# EasyGate1541_DIP-40.net
KiCad netlist of a schematic drawn in Altium Designer
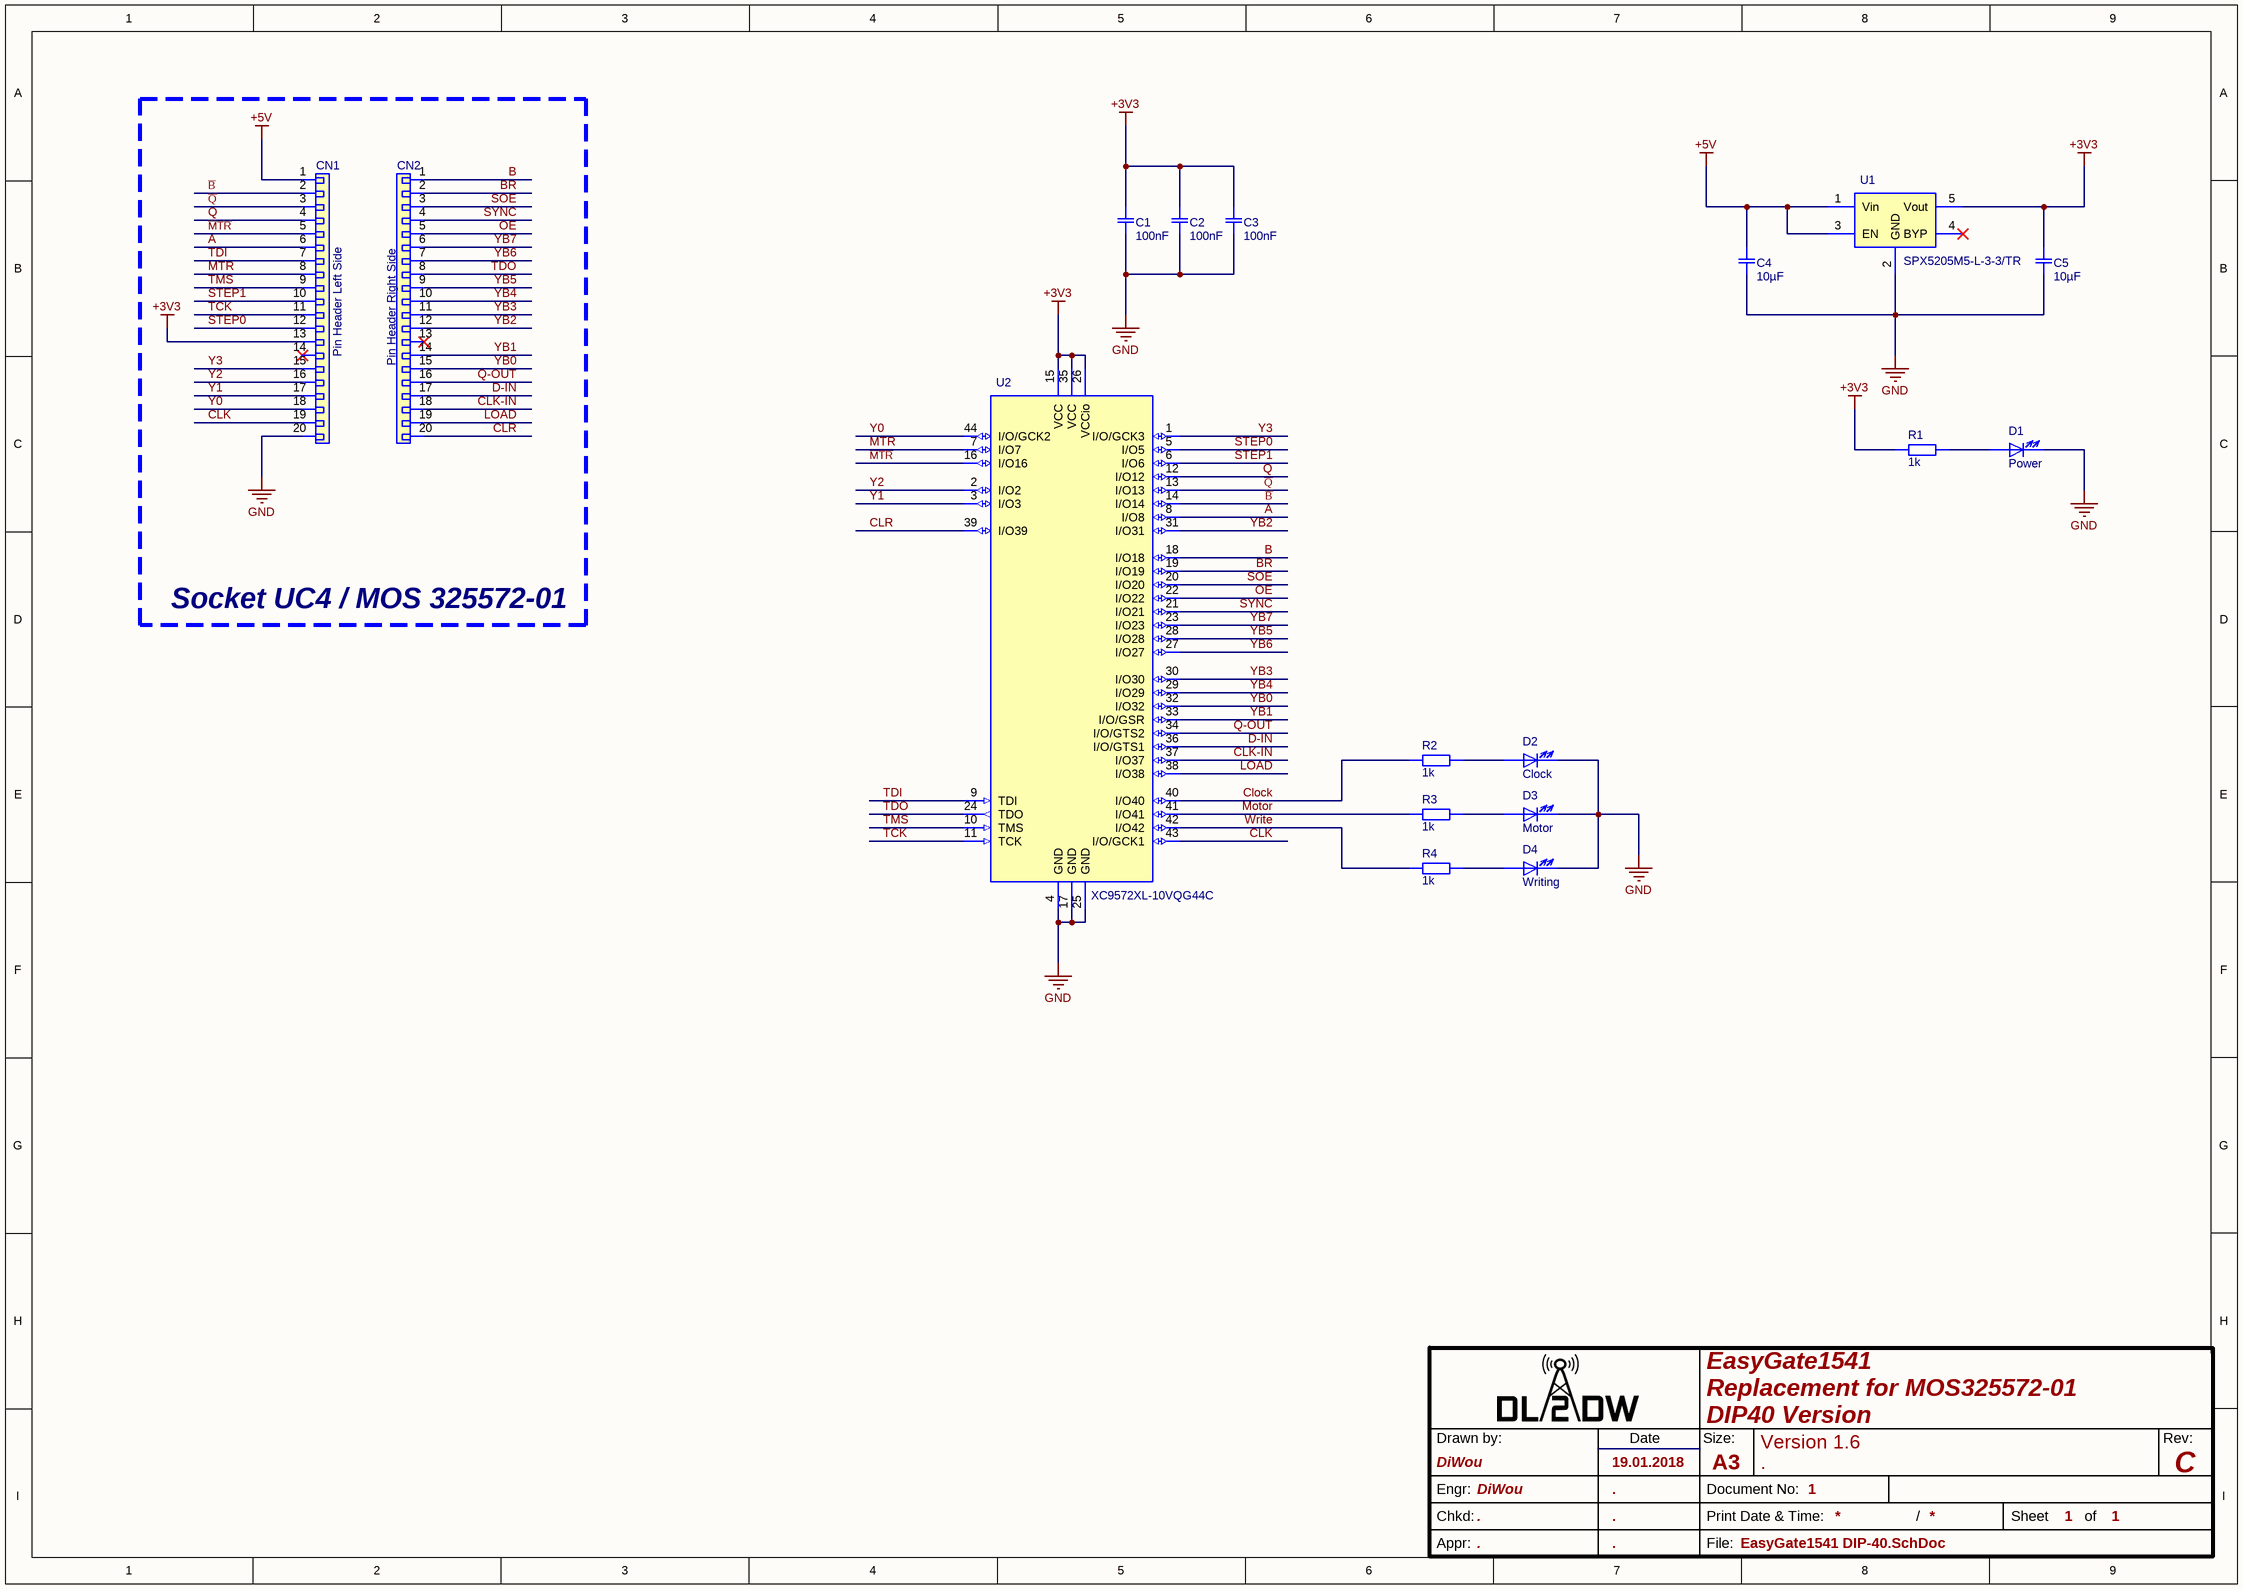
[diagram p0: EasyGate1541 DIP-40.SchDoc]

(export (version "E")
  (design (tool "Eeschema 10.0.6"))
  (components
    (comp (ref "C1")
      (value "100nF")
      (footprint "CAP 100nF SMD 0603 C0603C104J3RACTU")
      (fields (field (name "TOLERANCE") "5%") (field (name "VOLTAGE") "25V"))
      (libsource (lib "PCB-Tech Cloud") (part "Capacitor"))
    )
    (comp (ref "C2")
      (value "100nF")
      (footprint "CAP 100nF SMD 0603 C0603C104J3RACTU")
      (fields (field (name "TOLERANCE") "5%") (field (name "VOLTAGE") "25V"))
      (libsource (lib "PCB-Tech Cloud") (part "Capacitor"))
    )
    (comp (ref "C3")
      (value "100nF")
      (footprint "CAP 100nF SMD 0603 C0603C104J3RACTU")
      (fields (field (name "TOLERANCE") "5%") (field (name "VOLTAGE") "25V"))
      (libsource (lib "PCB-Tech Cloud") (part "Capacitor"))
    )
    (comp (ref "C4")
      (value "10µF")
      (footprint "Kemet C0805CxxxK8RACTU Series H=1.4mm")
      (description "KEMET - C0805C106K8RACTU - CAP, 10µF, 10V, 10%, X7R, 0805")
      (fields (field (name "VOLTAGE") "10V") (field (name "TOLERANCE") "10%"))
      (libsource (lib "PCB-Tech Cloud") (part "Capacitor"))
    )
    (comp (ref "C5")
      (value "10µF")
      (footprint "Kemet C0805CxxxK8RACTU Series H=1.4mm")
      (description "KEMET - C0805C106K8RACTU - CAP, 10µF, 10V, 10%, X7R, 0805")
      (fields (field (name "VOLTAGE") "10V") (field (name "TOLERANCE") "10%"))
      (libsource (lib "PCB-Tech Cloud") (part "Capacitor"))
    )
    (comp (ref "CN1")
      (value "Pin Header Left Side")
      (footprint "Pin Header 01x20 2.54mm precision Horizontal Male")
      (description "Conn Header Vert 20POS 2MM")
      (libsource (lib "") (part "CONN 01x20_1"))
    )
    (comp (ref "CN2")
      (value "Pin Header Right Side")
      (footprint "Pin Header 01x20 2.54mm precision Horizontal Male")
      (description "Conn Header Vert 20POS 2MM")
      (libsource (lib "PCB-Tech Cloud") (part "CONN 01x20"))
    )
    (comp (ref "D1")
      (value "Power")
      (footprint "LED green Gullwing Everlight 25-21/GHC-YSU/2A")
      (description "LED Uni-Color Green 518nm 2-Pin Chip LED T/R")
      (libsource (lib "PCB-Tech Cloud") (part "LED Standard"))
    )
    (comp (ref "D2")
      (value "Clock")
      (footprint "LED blue Gullwing Everlight 25-21/BHC-XR2S1/2A")
      (description "LED Uni-Color Blue 468nm Chip LED 2-Pin SMD T/R")
      (libsource (lib "PCB-Tech Cloud") (part "LED Standard"))
    )
    (comp (ref "D3")
      (value "Motor")
      (footprint "LED white Gullwing Everlight 25-21/T1D-ANQHY/2A")
      (description "Standard LEDs - SMD SMD LED")
      (libsource (lib "PCB-Tech Cloud") (part "LED Standard"))
    )
    (comp (ref "D4")
      (value "Writing")
      (footprint "LED red Gullwing Everlight 25-21SURC/S530-A4/TR8")
      (description "SMD LED red 2.7. . .3.15 V Bottom View, 25-21SURC/S530-A4/TR8, Everlight Electronics")
      (libsource (lib "PCB-Tech Cloud") (part "LED Standard"))
    )
    (comp (ref "R1")
      (value "1k")
      (footprint "1k Ohm R 0603 SMD")
      (description "RES SMD 1K OHM 1% 1/10W 0603")
      (fields (field (name "TOLERANCE") "1%"))
      (libsource (lib "PCB-Tech Cloud") (part "Resistor"))
    )
    (comp (ref "R2")
      (value "1k")
      (footprint "1k Ohm R 0603 SMD")
      (description "RES SMD 1K OHM 1% 1/10W 0603")
      (fields (field (name "TOLERANCE") "1%"))
      (libsource (lib "PCB-Tech Cloud") (part "Resistor"))
    )
    (comp (ref "R3")
      (value "1k")
      (footprint "1k Ohm R 0603 SMD")
      (description "RES SMD 1K OHM 1% 1/10W 0603")
      (fields (field (name "TOLERANCE") "1%"))
      (libsource (lib "PCB-Tech Cloud") (part "Resistor"))
    )
    (comp (ref "R4")
      (value "1k")
      (footprint "1k Ohm R 0603 SMD")
      (description "RES SMD 1K OHM 1% 1/10W 0603")
      (fields (field (name "TOLERANCE") "1%"))
      (libsource (lib "PCB-Tech Cloud") (part "Resistor"))
    )
    (comp (ref "U1")
      (value "SPX5205M5-L-3-3/TR")
      (footprint "SOT-23-5")
      (description "LDO Regulator Pos 3.3V 0.15A 5-Pin SOT-23 T/R")
      (libsource (lib "PCB-Tech Cloud") (part "SPX5205M5-L-3-3/TR"))
    )
    (comp (ref "U2")
      (value "XC9572XL-10VQG44C")
      (footprint "XC9572XL-10VQG44C")
      (description "XILINX - XC9572XL-10VQG44C. - CPLD, 72 MACROCELL, 3.3V, 44VQFP")
      (libsource (lib "PCB-Tech Cloud") (part "XC9572XL-10VQG44C"))
    )
  )
  (nets
    (net (code "1") (name "+3V3") (class "Default")
      (node (ref "C1") (pin "2") (pinfunction "2_2") (pintype "passive"))
      (node (ref "C2") (pin "2") (pinfunction "2_2") (pintype "passive"))
      (node (ref "C3") (pin "2") (pinfunction "2_2") (pintype "passive"))
      (node (ref "C5") (pin "2") (pinfunction "2_2") (pintype "passive"))
      (node (ref "CN1") (pin "13") (pinfunction "13_13") (pintype "passive"))
      (node (ref "R1") (pin "1") (pinfunction "1_1") (pintype "passive"))
      (node (ref "U1") (pin "5") (pinfunction "Vout_5") (pintype "power_in"))
      (node (ref "U2") (pin "15") (pinfunction "VCC_15") (pintype "power_in"))
      (node (ref "U2") (pin "26") (pinfunction "VCCio_26") (pintype "power_in"))
      (node (ref "U2") (pin "35") (pinfunction "VCC_35") (pintype "power_in"))
    )
    (net (code "2") (name "+5V") (class "Default")
      (node (ref "C4") (pin "2") (pinfunction "2_2") (pintype "passive"))
      (node (ref "CN1") (pin "1") (pinfunction "1_1") (pintype "passive"))
      (node (ref "U1") (pin "1") (pinfunction "Vin_1") (pintype "power_in"))
      (node (ref "U1") (pin "3") (pinfunction "EN_3") (pintype "passive"))
    )
    (net (code "3") (name "/A") (class "Default")
      (node (ref "CN1") (pin "6") (pinfunction "6_6") (pintype "passive"))
      (node (ref "U2") (pin "8") (pinfunction "I/O8_8") (pintype "bidirectional"))
    )
    (net (code "4") (name "/B") (class "Default")
      (node (ref "CN2") (pin "1") (pinfunction "1_1") (pintype "passive"))
      (node (ref "U2") (pin "18") (pinfunction "I/O18_18") (pintype "bidirectional"))
    )
    (net (code "5") (name "/BR") (class "Default")
      (node (ref "CN2") (pin "2") (pinfunction "2_2") (pintype "passive"))
      (node (ref "U2") (pin "19") (pinfunction "I/O19_19") (pintype "bidirectional"))
    )
    (net (code "6") (name "/CLK") (class "Default")
      (node (ref "CN1") (pin "19") (pinfunction "19_19") (pintype "passive"))
      (node (ref "U2") (pin "43") (pinfunction "I/O/GCK1_43") (pintype "bidirectional"))
    )
    (net (code "7") (name "/CLK-IN") (class "Default")
      (node (ref "CN2") (pin "18") (pinfunction "18_18") (pintype "passive"))
      (node (ref "U2") (pin "37") (pinfunction "I/O37_37") (pintype "bidirectional"))
    )
    (net (code "8") (name "/CLR") (class "Default")
      (node (ref "CN2") (pin "20") (pinfunction "20_20") (pintype "passive"))
      (node (ref "U2") (pin "39") (pinfunction "I/O39_39") (pintype "bidirectional"))
    )
    (net (code "9") (name "/Clock") (class "Default")
      (node (ref "R2") (pin "1") (pinfunction "1_1") (pintype "passive"))
      (node (ref "U2") (pin "40") (pinfunction "I/O40_40") (pintype "bidirectional"))
    )
    (net (code "10") (name "/D-IN") (class "Default")
      (node (ref "CN2") (pin "17") (pinfunction "17_17") (pintype "passive"))
      (node (ref "U2") (pin "36") (pinfunction "I/O/GTS1_36") (pintype "bidirectional"))
    )
    (net (code "11") (name "/LOAD") (class "Default")
      (node (ref "CN2") (pin "19") (pinfunction "19_19") (pintype "passive"))
      (node (ref "U2") (pin "38") (pinfunction "I/O38_38") (pintype "bidirectional"))
    )
    (net (code "12") (name "/MTR") (class "Default")
      (node (ref "CN1") (pin "8") (pinfunction "8_8") (pintype "passive"))
      (node (ref "U2") (pin "7") (pinfunction "I/O7_7") (pintype "bidirectional"))
    )
    (net (code "13") (name "/Motor") (class "Default")
      (node (ref "R3") (pin "1") (pinfunction "1_1") (pintype "passive"))
      (node (ref "U2") (pin "41") (pinfunction "I/O41_41") (pintype "bidirectional"))
    )
    (net (code "14") (name "/OE") (class "Default")
      (node (ref "CN2") (pin "5") (pinfunction "5_5") (pintype "passive"))
      (node (ref "U2") (pin "22") (pinfunction "I/O22_22") (pintype "bidirectional"))
    )
    (net (code "15") (name "/Q") (class "Default")
      (node (ref "CN1") (pin "4") (pinfunction "4_4") (pintype "passive"))
      (node (ref "U2") (pin "12") (pinfunction "I/O12_12") (pintype "bidirectional"))
    )
    (net (code "16") (name "/Q-OUT") (class "Default")
      (node (ref "CN2") (pin "16") (pinfunction "16_16") (pintype "passive"))
      (node (ref "U2") (pin "34") (pinfunction "I/O/GTS2_34") (pintype "bidirectional"))
    )
    (net (code "17") (name "/SOE") (class "Default")
      (node (ref "CN2") (pin "3") (pinfunction "3_3") (pintype "passive"))
      (node (ref "U2") (pin "20") (pinfunction "I/O20_20") (pintype "bidirectional"))
    )
    (net (code "18") (name "/STEP0") (class "Default")
      (node (ref "CN1") (pin "12") (pinfunction "12_12") (pintype "passive"))
      (node (ref "U2") (pin "5") (pinfunction "I/O5_5") (pintype "bidirectional"))
    )
    (net (code "19") (name "/STEP1") (class "Default")
      (node (ref "CN1") (pin "10") (pinfunction "10_10") (pintype "passive"))
      (node (ref "U2") (pin "6") (pinfunction "I/O6_6") (pintype "bidirectional"))
    )
    (net (code "20") (name "/SYNC") (class "Default")
      (node (ref "CN2") (pin "4") (pinfunction "4_4") (pintype "passive"))
      (node (ref "U2") (pin "21") (pinfunction "I/O21_21") (pintype "bidirectional"))
    )
    (net (code "21") (name "/TCK") (class "Default")
      (node (ref "CN1") (pin "11") (pinfunction "11_11") (pintype "passive"))
      (node (ref "U2") (pin "11") (pinfunction "TCK_11") (pintype "input"))
    )
    (net (code "22") (name "/TDI") (class "Default")
      (node (ref "CN1") (pin "7") (pinfunction "7_7") (pintype "passive"))
      (node (ref "U2") (pin "9") (pinfunction "TDI_9") (pintype "input"))
    )
    (net (code "23") (name "/TDO") (class "Default")
      (node (ref "CN2") (pin "8") (pinfunction "8_8") (pintype "passive"))
      (node (ref "U2") (pin "24") (pinfunction "TDO_24") (pintype "output"))
    )
    (net (code "24") (name "/TMS") (class "Default")
      (node (ref "CN1") (pin "9") (pinfunction "9_9") (pintype "passive"))
      (node (ref "U2") (pin "10") (pinfunction "TMS_10") (pintype "input"))
    )
    (net (code "25") (name "/Write") (class "Default")
      (node (ref "R4") (pin "1") (pinfunction "1_1") (pintype "passive"))
      (node (ref "U2") (pin "42") (pinfunction "I/O42_42") (pintype "bidirectional"))
    )
    (net (code "26") (name "/Y0") (class "Default")
      (node (ref "CN1") (pin "18") (pinfunction "18_18") (pintype "passive"))
      (node (ref "U2") (pin "44") (pinfunction "I/O/GCK2_44") (pintype "bidirectional"))
    )
    (net (code "27") (name "/Y1") (class "Default")
      (node (ref "CN1") (pin "17") (pinfunction "17_17") (pintype "passive"))
      (node (ref "U2") (pin "3") (pinfunction "I/O3_3") (pintype "bidirectional"))
    )
    (net (code "28") (name "/Y2") (class "Default")
      (node (ref "CN1") (pin "16") (pinfunction "16_16") (pintype "passive"))
      (node (ref "U2") (pin "2") (pinfunction "I/O2_2") (pintype "bidirectional"))
    )
    (net (code "29") (name "/Y3") (class "Default")
      (node (ref "CN1") (pin "15") (pinfunction "15_15") (pintype "passive"))
      (node (ref "U2") (pin "1") (pinfunction "I/O/GCK3_1") (pintype "bidirectional"))
    )
    (net (code "30") (name "/YB0") (class "Default")
      (node (ref "CN2") (pin "15") (pinfunction "15_15") (pintype "passive"))
      (node (ref "U2") (pin "32") (pinfunction "I/O32_32") (pintype "bidirectional"))
    )
    (net (code "31") (name "/YB1") (class "Default")
      (node (ref "CN2") (pin "14") (pinfunction "14_14") (pintype "passive"))
      (node (ref "U2") (pin "33") (pinfunction "I/O/GSR_33") (pintype "bidirectional"))
    )
    (net (code "32") (name "/YB2") (class "Default")
      (node (ref "CN2") (pin "12") (pinfunction "12_12") (pintype "passive"))
      (node (ref "U2") (pin "31") (pinfunction "I/O31_31") (pintype "bidirectional"))
    )
    (net (code "33") (name "/YB3") (class "Default")
      (node (ref "CN2") (pin "11") (pinfunction "11_11") (pintype "passive"))
      (node (ref "U2") (pin "30") (pinfunction "I/O30_30") (pintype "bidirectional"))
    )
    (net (code "34") (name "/YB4") (class "Default")
      (node (ref "CN2") (pin "10") (pinfunction "10_10") (pintype "passive"))
      (node (ref "U2") (pin "29") (pinfunction "I/O29_29") (pintype "bidirectional"))
    )
    (net (code "35") (name "/YB5") (class "Default")
      (node (ref "CN2") (pin "9") (pinfunction "9_9") (pintype "passive"))
      (node (ref "U2") (pin "28") (pinfunction "I/O28_28") (pintype "bidirectional"))
    )
    (net (code "36") (name "/YB6") (class "Default")
      (node (ref "CN2") (pin "7") (pinfunction "7_7") (pintype "passive"))
      (node (ref "U2") (pin "27") (pinfunction "I/O27_27") (pintype "bidirectional"))
    )
    (net (code "37") (name "/YB7") (class "Default")
      (node (ref "CN2") (pin "6") (pinfunction "6_6") (pintype "passive"))
      (node (ref "U2") (pin "23") (pinfunction "I/O23_23") (pintype "bidirectional"))
    )
    (net (code "38") (name "/~{B}") (class "Default")
      (node (ref "CN1") (pin "2") (pinfunction "2_2") (pintype "passive"))
      (node (ref "U2") (pin "14") (pinfunction "I/O14_14") (pintype "bidirectional"))
    )
    (net (code "39") (name "/~{MTR}") (class "Default")
      (node (ref "CN1") (pin "5") (pinfunction "5_5") (pintype "passive"))
      (node (ref "U2") (pin "16") (pinfunction "I/O16_16") (pintype "bidirectional"))
    )
    (net (code "40") (name "/~{Q}") (class "Default")
      (node (ref "CN1") (pin "3") (pinfunction "3_3") (pintype "passive"))
      (node (ref "U2") (pin "13") (pinfunction "I/O13_13") (pintype "bidirectional"))
    )
    (net (code "41") (name "GND") (class "Default")
      (node (ref "C1") (pin "1") (pinfunction "1_1") (pintype "passive"))
      (node (ref "C2") (pin "1") (pinfunction "1_1") (pintype "passive"))
      (node (ref "C3") (pin "1") (pinfunction "1_1") (pintype "passive"))
      (node (ref "C4") (pin "1") (pinfunction "1_1") (pintype "passive"))
      (node (ref "C5") (pin "1") (pinfunction "1_1") (pintype "passive"))
      (node (ref "CN1") (pin "20") (pinfunction "20_20") (pintype "passive"))
      (node (ref "D1") (pin "1") (pinfunction "1_1") (pintype "passive"))
      (node (ref "D2") (pin "1") (pinfunction "1_1") (pintype "passive"))
      (node (ref "D3") (pin "1") (pinfunction "1_1") (pintype "passive"))
      (node (ref "D4") (pin "1") (pinfunction "1_1") (pintype "passive"))
      (node (ref "U1") (pin "2") (pinfunction "GND_2") (pintype "power_in"))
      (node (ref "U2") (pin "17") (pinfunction "GND_17") (pintype "power_in"))
      (node (ref "U2") (pin "25") (pinfunction "GND_25") (pintype "power_in"))
      (node (ref "U2") (pin "4") (pinfunction "GND_4") (pintype "power_in"))
    )
    (net (code "42") (name "Net-(D1-Pad2)") (class "Default")
      (node (ref "D1") (pin "2") (pinfunction "2_2") (pintype "passive"))
      (node (ref "R1") (pin "2") (pinfunction "2_2") (pintype "passive"))
    )
    (net (code "43") (name "Net-(D2-Pad2)") (class "Default")
      (node (ref "D2") (pin "2") (pinfunction "2_2") (pintype "passive"))
      (node (ref "R2") (pin "2") (pinfunction "2_2") (pintype "passive"))
    )
    (net (code "44") (name "Net-(D3-Pad2)") (class "Default")
      (node (ref "D3") (pin "2") (pinfunction "2_2") (pintype "passive"))
      (node (ref "R3") (pin "2") (pinfunction "2_2") (pintype "passive"))
    )
    (net (code "45") (name "Net-(D4-Pad2)") (class "Default")
      (node (ref "D4") (pin "2") (pinfunction "2_2") (pintype "passive"))
      (node (ref "R4") (pin "2") (pinfunction "2_2") (pintype "passive"))
    )
    (net (code "46") (name "unconnected-(CN1-Pad14)") (class "Default")
      (node (ref "CN1") (pin "14") (pinfunction "14_14") (pintype "passive+no_connect"))
    )
    (net (code "47") (name "unconnected-(CN2-Pad13)") (class "Default")
      (node (ref "CN2") (pin "13") (pinfunction "13_13") (pintype "passive+no_connect"))
    )
    (net (code "48") (name "unconnected-(U1-BYP-Pad4)") (class "Default")
      (node (ref "U1") (pin "4") (pinfunction "BYP_4") (pintype "passive+no_connect"))
    )
  )
)
